# 02-bluetooth-V2_4.net
KiCad netlist of a schematic drawn in Altium Designer
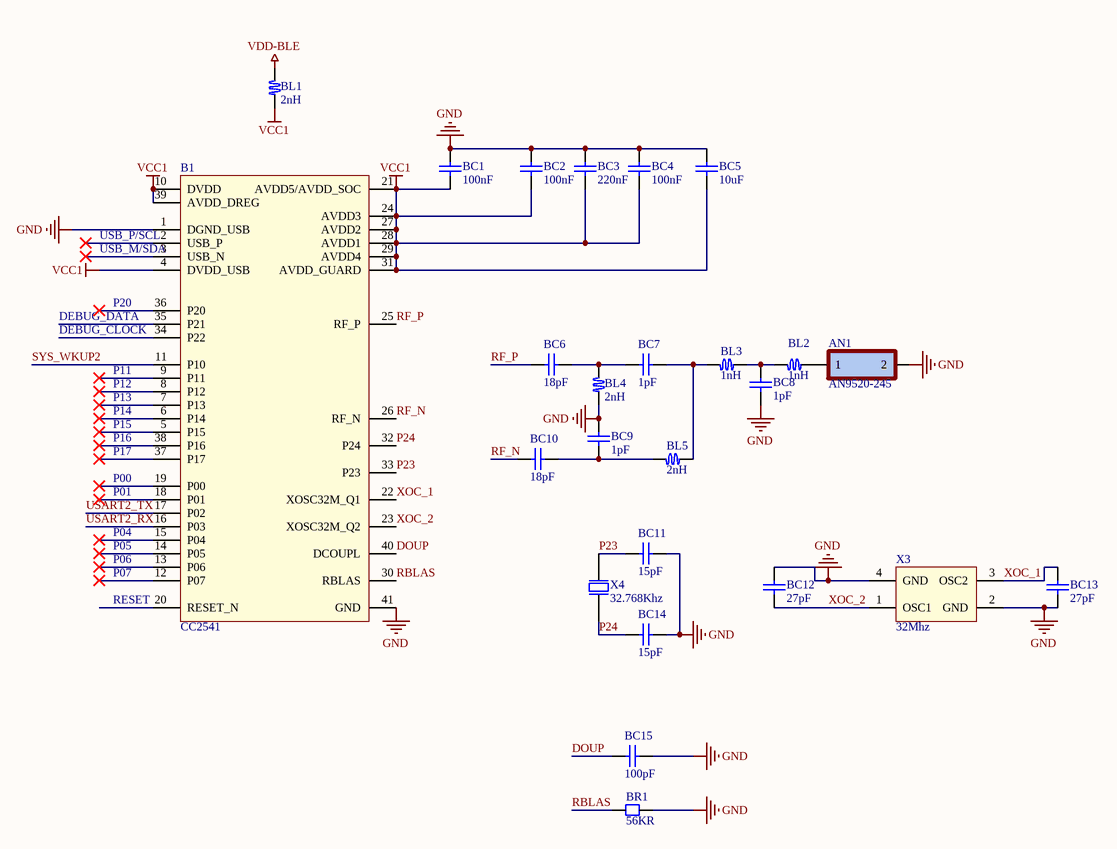
[diagram p0: 02-bluetooth-V2.4.SchDoc]

(export (version "E")
  (design (tool "Eeschema 10.0.6"))
  (components
    (comp (ref "AN1")
      (value "AN9520-245")
      (footprint "AN-5120")
      (description "2.4G全向天线 蓝牙天线 陶瓷贴片 WIFI内置")
      (libsource (lib "tianxiaohua_Schlib") (part "AN9520-245"))
    )
    (comp (ref "B1")
      (value "CC2541")
      (footprint "QFN40-CC254X")
      (description "低功耗蓝牙芯片")
      (libsource (lib "tianxiaohua_Schlib") (part "CC2541"))
    )
    (comp (ref "BC1")
      (value "100nF")
      (footprint "CC1005-0402")
      (description "贴片电容")
      (libsource (lib "tianxiaohua_Schlib") (part "Chip capacitor"))
    )
    (comp (ref "BC2")
      (value "100nF")
      (footprint "CC1005-0402")
      (description "贴片电容")
      (libsource (lib "tianxiaohua_Schlib") (part "Chip capacitor"))
    )
    (comp (ref "BC3")
      (value "220nF")
      (footprint "CC1005-0402")
      (description "贴片电容")
      (libsource (lib "tianxiaohua_Schlib") (part "Chip capacitor"))
    )
    (comp (ref "BC4")
      (value "100nF")
      (footprint "CC1005-0402")
      (description "贴片电容")
      (libsource (lib "tianxiaohua_Schlib") (part "Chip capacitor"))
    )
    (comp (ref "BC5")
      (value "10uF")
      (footprint "CC1005-0402")
      (description "贴片电容")
      (libsource (lib "tianxiaohua_Schlib") (part "Chip capacitor"))
    )
    (comp (ref "BC6")
      (value "18pF")
      (footprint "CC1005-0402")
      (description "贴片电容")
      (libsource (lib "tianxiaohua_Schlib") (part "Chip capacitor"))
    )
    (comp (ref "BC7")
      (value "1pF")
      (footprint "CC1005-0402")
      (description "贴片电容")
      (libsource (lib "tianxiaohua_Schlib") (part "Chip capacitor"))
    )
    (comp (ref "BC8")
      (value "1pF")
      (footprint "CC1005-0402")
      (description "贴片电容")
      (libsource (lib "tianxiaohua_Schlib") (part "Chip capacitor"))
    )
    (comp (ref "BC9")
      (value "1pF")
      (footprint "CC1005-0402")
      (description "贴片电容")
      (libsource (lib "tianxiaohua_Schlib") (part "Chip capacitor"))
    )
    (comp (ref "BC10")
      (value "18pF")
      (footprint "CC1005-0402")
      (description "贴片电容")
      (libsource (lib "tianxiaohua_Schlib") (part "Chip capacitor"))
    )
    (comp (ref "BC11")
      (value "15pF")
      (footprint "CC1005-0402")
      (description "贴片电容")
      (libsource (lib "tianxiaohua_Schlib") (part "Chip capacitor"))
    )
    (comp (ref "BC12")
      (value "27pF")
      (footprint "CC1005-0402")
      (description "贴片电容")
      (libsource (lib "tianxiaohua_Schlib") (part "Chip capacitor"))
    )
    (comp (ref "BC13")
      (value "27pF")
      (footprint "CC1005-0402")
      (description "贴片电容")
      (libsource (lib "tianxiaohua_Schlib") (part "Chip capacitor"))
    )
    (comp (ref "BC14")
      (value "15pF")
      (footprint "CC1005-0402")
      (description "贴片电容")
      (libsource (lib "tianxiaohua_Schlib") (part "Chip capacitor"))
    )
    (comp (ref "BC15")
      (value "100pF")
      (footprint "CC1005-0402")
      (description "贴片电容")
      (libsource (lib "tianxiaohua_Schlib") (part "Chip capacitor"))
    )
    (comp (ref "BL1")
      (value "2nH")
      (footprint "Inductor-0402")
      (description "0402封装的电感")
      (libsource (lib "") (part "Inductor-0402_1"))
    )
    (comp (ref "BL2")
      (value "1nH")
      (footprint "Inductor-0402")
      (description "0402封装的电感")
      (libsource (lib "tianxiaohua_Schlib") (part "Inductor-0402"))
    )
    (comp (ref "BL3")
      (value "1nH")
      (footprint "Inductor-0402")
      (description "0402封装的电感")
      (libsource (lib "tianxiaohua_Schlib") (part "Inductor-0402"))
    )
    (comp (ref "BL4")
      (value "2nH")
      (footprint "Inductor-0402")
      (description "0402封装的电感")
      (libsource (lib "") (part "Inductor-0402_1"))
    )
    (comp (ref "BL5")
      (value "2nH")
      (footprint "Inductor-0402")
      (description "0402封装的电感")
      (libsource (lib "tianxiaohua_Schlib") (part "Inductor-0402"))
    )
    (comp (ref "BR1")
      (value "56KR")
      (footprint "CR1005-0402")
      (description "贴片电阻")
      (libsource (lib "tianxiaohua_Schlib") (part "Chip resistor"))
    )
    (comp (ref "X3")
      (value "32Mhz")
      (footprint "XTAL-2016")
      (description "2016封装的晶振")
      (libsource (lib "tianxiaohua_Schlib") (part "XTAL 2016"))
    )
    (comp (ref "X4")
      (value "32.768Khz")
      (footprint "XTAL-2012")
      (description "2012封装的时钟晶振")
      (libsource (lib "tianxiaohua_Schlib") (part "XTAL 2012"))
    )
  )
  (nets
    (net (code "1") (name "/DEBUG_CLOCK") (class "Default")
      (node (ref "B1") (pin "34") (pinfunction "P22_34") (pintype "passive"))
    )
    (net (code "2") (name "/DEBUG_DATA") (class "Default")
      (node (ref "B1") (pin "35") (pinfunction "P21_35") (pintype "passive"))
    )
    (net (code "3") (name "/DOUP") (class "Default")
      (node (ref "B1") (pin "40") (pinfunction "DCOUPL_40") (pintype "passive"))
      (node (ref "BC15") (pin "2") (pinfunction "2_2") (pintype "passive"))
    )
    (net (code "4") (name "/P00") (class "Default")
      (node (ref "B1") (pin "19") (pinfunction "P00_19") (pintype "passive+no_connect"))
    )
    (net (code "5") (name "/P01") (class "Default")
      (node (ref "B1") (pin "18") (pinfunction "P01_18") (pintype "passive+no_connect"))
    )
    (net (code "6") (name "/P04") (class "Default")
      (node (ref "B1") (pin "15") (pinfunction "P04_15") (pintype "passive+no_connect"))
    )
    (net (code "7") (name "/P05") (class "Default")
      (node (ref "B1") (pin "14") (pinfunction "P05_14") (pintype "passive+no_connect"))
    )
    (net (code "8") (name "/P06") (class "Default")
      (node (ref "B1") (pin "13") (pinfunction "P06_13") (pintype "passive+no_connect"))
    )
    (net (code "9") (name "/P07") (class "Default")
      (node (ref "B1") (pin "12") (pinfunction "P07_12") (pintype "passive+no_connect"))
    )
    (net (code "10") (name "/P11") (class "Default")
      (node (ref "B1") (pin "9") (pinfunction "P11_9") (pintype "passive+no_connect"))
    )
    (net (code "11") (name "/P12") (class "Default")
      (node (ref "B1") (pin "8") (pinfunction "P12_8") (pintype "passive+no_connect"))
    )
    (net (code "12") (name "/P13") (class "Default")
      (node (ref "B1") (pin "7") (pinfunction "P13_7") (pintype "passive+no_connect"))
    )
    (net (code "13") (name "/P14") (class "Default")
      (node (ref "B1") (pin "6") (pinfunction "P14_6") (pintype "passive+no_connect"))
    )
    (net (code "14") (name "/P15") (class "Default")
      (node (ref "B1") (pin "5") (pinfunction "P15_5") (pintype "passive+no_connect"))
    )
    (net (code "15") (name "/P16") (class "Default")
      (node (ref "B1") (pin "38") (pinfunction "P16_38") (pintype "passive+no_connect"))
    )
    (net (code "16") (name "/P17") (class "Default")
      (node (ref "B1") (pin "37") (pinfunction "P17_37") (pintype "passive+no_connect"))
    )
    (net (code "17") (name "/P20") (class "Default")
      (node (ref "B1") (pin "36") (pinfunction "P20_36") (pintype "passive+no_connect"))
    )
    (net (code "18") (name "/P23") (class "Default")
      (node (ref "B1") (pin "33") (pinfunction "P23_33") (pintype "passive"))
      (node (ref "BC11") (pin "1") (pinfunction "1_1") (pintype "passive"))
      (node (ref "X4") (pin "2") (pinfunction "2_2") (pintype "passive"))
    )
    (net (code "19") (name "/P24") (class "Default")
      (node (ref "B1") (pin "32") (pinfunction "P24_32") (pintype "passive"))
      (node (ref "BC14") (pin "1") (pinfunction "1_1") (pintype "passive"))
      (node (ref "X4") (pin "1") (pinfunction "1_1") (pintype "passive"))
    )
    (net (code "20") (name "/RBLAS") (class "Default")
      (node (ref "B1") (pin "30") (pinfunction "RBLAS_30") (pintype "passive"))
      (node (ref "BR1") (pin "1") (pinfunction "1_1") (pintype "passive"))
    )
    (net (code "21") (name "/RESET") (class "Default")
      (node (ref "B1") (pin "20") (pinfunction "RESET_N_20") (pintype "passive"))
    )
    (net (code "22") (name "/RF_N") (class "Default")
      (node (ref "B1") (pin "26") (pinfunction "RF_N_26") (pintype "passive"))
      (node (ref "BC10") (pin "2") (pinfunction "2_2") (pintype "passive"))
    )
    (net (code "23") (name "/RF_P") (class "Default")
      (node (ref "B1") (pin "25") (pinfunction "RF_P_25") (pintype "passive"))
      (node (ref "BC6") (pin "2") (pinfunction "2_2") (pintype "passive"))
    )
    (net (code "24") (name "/SYS_WKUP2") (class "Default")
      (node (ref "B1") (pin "11") (pinfunction "P10_11") (pintype "passive"))
    )
    (net (code "25") (name "/USART2_RX") (class "Default")
      (node (ref "B1") (pin "16") (pinfunction "P03_16") (pintype "passive"))
    )
    (net (code "26") (name "/USART2_TX") (class "Default")
      (node (ref "B1") (pin "17") (pinfunction "P02_17") (pintype "passive"))
    )
    (net (code "27") (name "/USB_M{slash}SDA") (class "Default")
      (node (ref "B1") (pin "3") (pinfunction "USB_N_3") (pintype "passive+no_connect"))
    )
    (net (code "28") (name "/USB_P{slash}SCL") (class "Default")
      (node (ref "B1") (pin "2") (pinfunction "USB_P_2") (pintype "passive+no_connect"))
    )
    (net (code "29") (name "/XOC_1") (class "Default")
      (node (ref "B1") (pin "22") (pinfunction "XOSC32M_Q1_22") (pintype "passive"))
      (node (ref "BC13") (pin "2") (pinfunction "2_2") (pintype "passive"))
      (node (ref "X3") (pin "3") (pinfunction "OSC2_3") (pintype "passive"))
    )
    (net (code "30") (name "/XOC_2") (class "Default")
      (node (ref "B1") (pin "23") (pinfunction "XOSC32M_Q2_23") (pintype "passive"))
      (node (ref "BC12") (pin "1") (pinfunction "1_1") (pintype "passive"))
      (node (ref "X3") (pin "1") (pinfunction "OSC1_1") (pintype "passive"))
    )
    (net (code "31") (name "GND") (class "Default")
      (node (ref "AN1") (pin "2") (pinfunction "2_2") (pintype "passive"))
      (node (ref "B1") (pin "1") (pinfunction "DGND_USB_1") (pintype "passive"))
      (node (ref "B1") (pin "41") (pinfunction "GND_41") (pintype "passive"))
      (node (ref "BC1") (pin "2") (pinfunction "2_2") (pintype "passive"))
      (node (ref "BC11") (pin "2") (pinfunction "2_2") (pintype "passive"))
      (node (ref "BC12") (pin "2") (pinfunction "2_2") (pintype "passive"))
      (node (ref "BC13") (pin "1") (pinfunction "1_1") (pintype "passive"))
      (node (ref "BC14") (pin "2") (pinfunction "2_2") (pintype "passive"))
      (node (ref "BC15") (pin "1") (pinfunction "1_1") (pintype "passive"))
      (node (ref "BC2") (pin "2") (pinfunction "2_2") (pintype "passive"))
      (node (ref "BC3") (pin "2") (pinfunction "2_2") (pintype "passive"))
      (node (ref "BC4") (pin "2") (pinfunction "2_2") (pintype "passive"))
      (node (ref "BC5") (pin "2") (pinfunction "2_2") (pintype "passive"))
      (node (ref "BC8") (pin "1") (pinfunction "1_1") (pintype "passive"))
      (node (ref "BC9") (pin "1") (pinfunction "1_1") (pintype "passive"))
      (node (ref "BL4") (pin "1") (pinfunction "1_1") (pintype "passive"))
      (node (ref "BR1") (pin "2") (pinfunction "2_2") (pintype "passive"))
      (node (ref "X3") (pin "2") (pinfunction "GND_2") (pintype "passive"))
      (node (ref "X3") (pin "4") (pinfunction "GND_4") (pintype "passive"))
    )
    (net (code "32") (name "Net-(AN1-Pad1)") (class "Default")
      (node (ref "AN1") (pin "1") (pinfunction "1_1") (pintype "passive"))
      (node (ref "BL2") (pin "1") (pinfunction "1_1") (pintype "passive"))
    )
    (net (code "33") (name "Net-(BC6-Pad1)") (class "Default")
      (node (ref "BC6") (pin "1") (pinfunction "1_1") (pintype "passive"))
      (node (ref "BC7") (pin "1") (pinfunction "1_1") (pintype "passive"))
      (node (ref "BL4") (pin "2") (pinfunction "2_2") (pintype "passive"))
    )
    (net (code "34") (name "Net-(BC7-Pad2)") (class "Default")
      (node (ref "BC7") (pin "2") (pinfunction "2_2") (pintype "passive"))
      (node (ref "BL3") (pin "2") (pinfunction "2_2") (pintype "passive"))
      (node (ref "BL5") (pin "1") (pinfunction "1_1") (pintype "passive"))
    )
    (net (code "35") (name "Net-(BC8-Pad2)") (class "Default")
      (node (ref "BC8") (pin "2") (pinfunction "2_2") (pintype "passive"))
      (node (ref "BL2") (pin "2") (pinfunction "2_2") (pintype "passive"))
      (node (ref "BL3") (pin "1") (pinfunction "1_1") (pintype "passive"))
    )
    (net (code "36") (name "Net-(BC10-Pad1)") (class "Default")
      (node (ref "BC10") (pin "1") (pinfunction "1_1") (pintype "passive"))
      (node (ref "BC9") (pin "2") (pinfunction "2_2") (pintype "passive"))
      (node (ref "BL5") (pin "2") (pinfunction "2_2") (pintype "passive"))
    )
    (net (code "37") (name "VCC1") (class "Default")
      (node (ref "B1") (pin "10") (pinfunction "DVDD_10") (pintype "passive"))
      (node (ref "B1") (pin "21") (pinfunction "AVDD5/AVDD_SOC_21") (pintype "passive"))
      (node (ref "B1") (pin "24") (pinfunction "AVDD3_24") (pintype "passive"))
      (node (ref "B1") (pin "27") (pinfunction "AVDD2_27") (pintype "passive"))
      (node (ref "B1") (pin "28") (pinfunction "AVDD1_28") (pintype "passive"))
      (node (ref "B1") (pin "29") (pinfunction "AVDD4_29") (pintype "passive"))
      (node (ref "B1") (pin "31") (pinfunction "AVDD_GUARD_31") (pintype "passive"))
      (node (ref "B1") (pin "39") (pinfunction "AVDD_DREG_39") (pintype "passive"))
      (node (ref "B1") (pin "4") (pinfunction "DVDD_USB_4") (pintype "passive"))
      (node (ref "BC1") (pin "1") (pinfunction "1_1") (pintype "passive"))
      (node (ref "BC2") (pin "1") (pinfunction "1_1") (pintype "passive"))
      (node (ref "BC3") (pin "1") (pinfunction "1_1") (pintype "passive"))
      (node (ref "BC4") (pin "1") (pinfunction "1_1") (pintype "passive"))
      (node (ref "BC5") (pin "1") (pinfunction "1_1") (pintype "passive"))
      (node (ref "BL1") (pin "1") (pinfunction "1_1") (pintype "passive"))
    )
    (net (code "38") (name "VDD-BLE") (class "Default")
      (node (ref "BL1") (pin "2") (pinfunction "2_2") (pintype "passive"))
    )
  )
)
